# mic4606_power.net
KiCad netlist of a schematic drawn in EAGLE
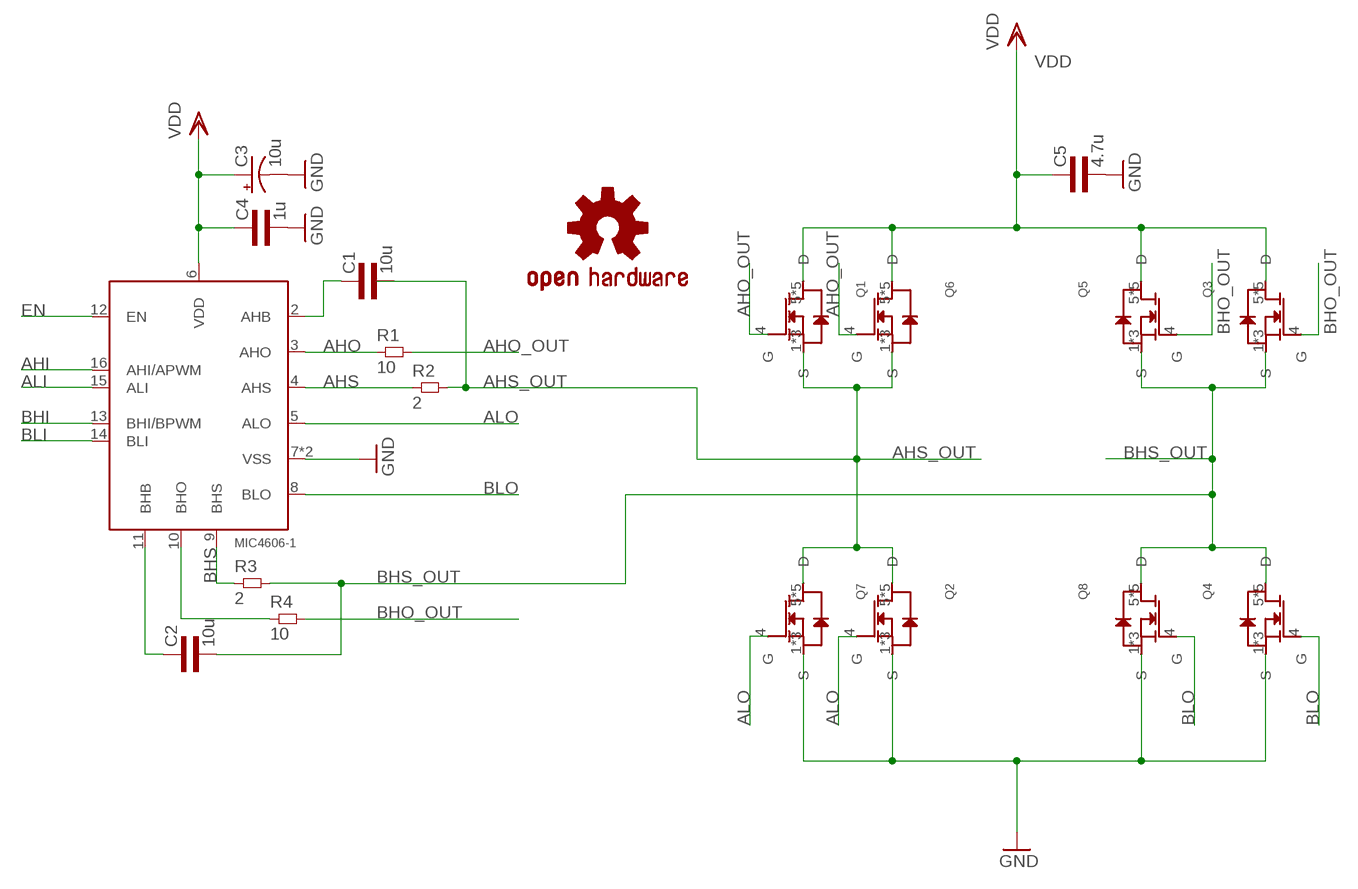
[diagram p0: schematic, sheet 1]

(export (version "E")
  (design (tool "Eeschema 10.0.6"))
  (components
    (comp (ref "C1")
      (value "10u")
      (footprint "eagle-import:0805L3")
      (libsource (lib "eagle-import") (part "CAP0805L3"))
    )
    (comp (ref "C2")
      (value "10u")
      (footprint "eagle-import:0805L3")
      (libsource (lib "eagle-import") (part "CAP0805L3"))
    )
    (comp (ref "C3")
      (value "10u")
      (footprint "eagle-import:E1,8-4")
      (libsource (lib "eagle-import") (part "CPOL-USE1.8-4"))
    )
    (comp (ref "C4")
      (value "1u")
      (footprint "eagle-import:0603L3")
      (libsource (lib "eagle-import") (part "CAP0603L3"))
    )
    (comp (ref "C5")
      (value "4.7u")
      (footprint "eagle-import:0805L3")
      (libsource (lib "eagle-import") (part "CAP0805L3"))
    )
    (comp (ref "LOGO1")
      (value "OSHW-LOGOM")
      (footprint "eagle-import:OSHW-LOGO-M")
      (libsource (lib "eagle-import") (part "OSHW-LOGOM"))
    )
    (comp (ref "MD1")
      (value "MIC4606-1")
      (footprint "eagle-import:QFN44-16LD-PL-2")
      (libsource (lib "eagle-import") (part "MIC4606-1"))
    )
    (comp (ref "Q1")
      (value "CSD18540Q5B")
      (footprint "eagle-import:Q5B")
      (libsource (lib "eagle-import") (part "CSD18540Q5B"))
    )
    (comp (ref "Q2")
      (value "CSD18540Q5B")
      (footprint "eagle-import:Q5B")
      (libsource (lib "eagle-import") (part "CSD18540Q5B"))
    )
    (comp (ref "Q3")
      (value "CSD18540Q5B")
      (footprint "eagle-import:Q5B")
      (libsource (lib "eagle-import") (part "CSD18540Q5B"))
    )
    (comp (ref "Q4")
      (value "CSD18540Q5B")
      (footprint "eagle-import:Q5B")
      (libsource (lib "eagle-import") (part "CSD18540Q5B"))
    )
    (comp (ref "Q5")
      (value "CSD18540Q5B")
      (footprint "eagle-import:Q5B")
      (libsource (lib "eagle-import") (part "CSD18540Q5B"))
    )
    (comp (ref "Q6")
      (value "CSD18540Q5B")
      (footprint "eagle-import:Q5B")
      (libsource (lib "eagle-import") (part "CSD18540Q5B"))
    )
    (comp (ref "Q7")
      (value "CSD18540Q5B")
      (footprint "eagle-import:Q5B")
      (libsource (lib "eagle-import") (part "CSD18540Q5B"))
    )
    (comp (ref "Q8")
      (value "CSD18540Q5B")
      (footprint "eagle-import:Q5B")
      (libsource (lib "eagle-import") (part "CSD18540Q5B"))
    )
    (comp (ref "R1")
      (value "10")
      (footprint "eagle-import:0805L3")
      (libsource (lib "eagle-import") (part "RES0805L3"))
    )
    (comp (ref "R2")
      (value "2")
      (footprint "eagle-import:0805L3")
      (libsource (lib "eagle-import") (part "RES0805L3"))
    )
    (comp (ref "R3")
      (value "2")
      (footprint "eagle-import:0805L3")
      (libsource (lib "eagle-import") (part "RES0805L3"))
    )
    (comp (ref "R4")
      (value "10")
      (footprint "eagle-import:0805L3")
      (libsource (lib "eagle-import") (part "RES0805L3"))
    )
  )
  (nets
    (net (code "1") (name "/AHI") (class "Default")
      (node (ref "MD1") (pin "16") (pinfunction "AHI/APWM_16") (pintype "bidirectional"))
    )
    (net (code "2") (name "/AHO") (class "Default")
      (node (ref "MD1") (pin "3") (pinfunction "AHO_3") (pintype "bidirectional"))
      (node (ref "R1") (pin "1") (pinfunction "1_1") (pintype "bidirectional"))
    )
    (net (code "3") (name "/AHO_OUT") (class "Default")
      (node (ref "Q1") (pin "4") (pinfunction "G_4") (pintype "bidirectional"))
      (node (ref "Q6") (pin "4") (pinfunction "G_4") (pintype "bidirectional"))
      (node (ref "R1") (pin "2") (pinfunction "2_2") (pintype "bidirectional"))
    )
    (net (code "4") (name "/AHS") (class "Default")
      (node (ref "MD1") (pin "4") (pinfunction "AHS_4") (pintype "bidirectional"))
      (node (ref "R2") (pin "1") (pinfunction "1_1") (pintype "bidirectional"))
    )
    (net (code "5") (name "/AHS_OUT") (class "Default")
      (node (ref "C1") (pin "2") (pinfunction "2_2") (pintype "bidirectional"))
      (node (ref "Q1") (pin "1") (pinfunction "S_1") (pintype "bidirectional"))
      (node (ref "Q1") (pin "2") (pinfunction "S_2") (pintype "bidirectional"))
      (node (ref "Q1") (pin "3") (pinfunction "S_3") (pintype "bidirectional"))
      (node (ref "Q2") (pin "5") (pinfunction "D_5") (pintype "bidirectional"))
      (node (ref "Q2") (pin "6") (pinfunction "D_6") (pintype "bidirectional"))
      (node (ref "Q2") (pin "7") (pinfunction "D_7") (pintype "bidirectional"))
      (node (ref "Q2") (pin "8") (pinfunction "D_8") (pintype "bidirectional"))
      (node (ref "Q2") (pin "9") (pinfunction "D_9") (pintype "bidirectional"))
      (node (ref "Q6") (pin "1") (pinfunction "S_1") (pintype "bidirectional"))
      (node (ref "Q6") (pin "2") (pinfunction "S_2") (pintype "bidirectional"))
      (node (ref "Q6") (pin "3") (pinfunction "S_3") (pintype "bidirectional"))
      (node (ref "Q7") (pin "5") (pinfunction "D_5") (pintype "bidirectional"))
      (node (ref "Q7") (pin "6") (pinfunction "D_6") (pintype "bidirectional"))
      (node (ref "Q7") (pin "7") (pinfunction "D_7") (pintype "bidirectional"))
      (node (ref "Q7") (pin "8") (pinfunction "D_8") (pintype "bidirectional"))
      (node (ref "Q7") (pin "9") (pinfunction "D_9") (pintype "bidirectional"))
      (node (ref "R2") (pin "2") (pinfunction "2_2") (pintype "bidirectional"))
    )
    (net (code "6") (name "/ALI") (class "Default")
      (node (ref "MD1") (pin "15") (pinfunction "ALI_15") (pintype "bidirectional"))
    )
    (net (code "7") (name "/ALO") (class "Default")
      (node (ref "MD1") (pin "5") (pinfunction "ALO_5") (pintype "bidirectional"))
      (node (ref "Q2") (pin "4") (pinfunction "G_4") (pintype "bidirectional"))
      (node (ref "Q7") (pin "4") (pinfunction "G_4") (pintype "bidirectional"))
    )
    (net (code "8") (name "/BHI") (class "Default")
      (node (ref "MD1") (pin "13") (pinfunction "BHI/BPWM_13") (pintype "bidirectional"))
    )
    (net (code "9") (name "/BHO_OUT") (class "Default")
      (node (ref "Q3") (pin "4") (pinfunction "G_4") (pintype "bidirectional"))
      (node (ref "Q5") (pin "4") (pinfunction "G_4") (pintype "bidirectional"))
      (node (ref "R4") (pin "2") (pinfunction "2_2") (pintype "bidirectional"))
    )
    (net (code "10") (name "/BHS") (class "Default")
      (node (ref "MD1") (pin "9") (pinfunction "BHS_9") (pintype "bidirectional"))
      (node (ref "R3") (pin "1") (pinfunction "1_1") (pintype "bidirectional"))
    )
    (net (code "11") (name "/BHS_OUT") (class "Default")
      (node (ref "C2") (pin "2") (pinfunction "2_2") (pintype "bidirectional"))
      (node (ref "Q3") (pin "1") (pinfunction "S_1") (pintype "bidirectional"))
      (node (ref "Q3") (pin "2") (pinfunction "S_2") (pintype "bidirectional"))
      (node (ref "Q3") (pin "3") (pinfunction "S_3") (pintype "bidirectional"))
      (node (ref "Q4") (pin "5") (pinfunction "D_5") (pintype "bidirectional"))
      (node (ref "Q4") (pin "6") (pinfunction "D_6") (pintype "bidirectional"))
      (node (ref "Q4") (pin "7") (pinfunction "D_7") (pintype "bidirectional"))
      (node (ref "Q4") (pin "8") (pinfunction "D_8") (pintype "bidirectional"))
      (node (ref "Q4") (pin "9") (pinfunction "D_9") (pintype "bidirectional"))
      (node (ref "Q5") (pin "1") (pinfunction "S_1") (pintype "bidirectional"))
      (node (ref "Q5") (pin "2") (pinfunction "S_2") (pintype "bidirectional"))
      (node (ref "Q5") (pin "3") (pinfunction "S_3") (pintype "bidirectional"))
      (node (ref "Q8") (pin "5") (pinfunction "D_5") (pintype "bidirectional"))
      (node (ref "Q8") (pin "6") (pinfunction "D_6") (pintype "bidirectional"))
      (node (ref "Q8") (pin "7") (pinfunction "D_7") (pintype "bidirectional"))
      (node (ref "Q8") (pin "8") (pinfunction "D_8") (pintype "bidirectional"))
      (node (ref "Q8") (pin "9") (pinfunction "D_9") (pintype "bidirectional"))
      (node (ref "R3") (pin "2") (pinfunction "2_2") (pintype "bidirectional"))
    )
    (net (code "12") (name "/BLI") (class "Default")
      (node (ref "MD1") (pin "14") (pinfunction "BLI_14") (pintype "bidirectional"))
    )
    (net (code "13") (name "/BLO") (class "Default")
      (node (ref "MD1") (pin "8") (pinfunction "BLO_8") (pintype "bidirectional"))
      (node (ref "Q4") (pin "4") (pinfunction "G_4") (pintype "bidirectional"))
      (node (ref "Q8") (pin "4") (pinfunction "G_4") (pintype "bidirectional"))
    )
    (net (code "14") (name "/EN") (class "Default")
      (node (ref "MD1") (pin "12") (pinfunction "EN_12") (pintype "bidirectional"))
    )
    (net (code "15") (name "GND") (class "Default")
      (node (ref "C3") (pin "-") (pinfunction "-_-") (pintype "passive"))
      (node (ref "C4") (pin "P$2") (pinfunction "2_P$2") (pintype "bidirectional"))
      (node (ref "C5") (pin "2") (pinfunction "2_2") (pintype "bidirectional"))
      (node (ref "MD1") (pin "7") (pinfunction "VSS_7") (pintype "bidirectional"))
      (node (ref "MD1") (pin "TP") (pinfunction "VSS_TP") (pintype "bidirectional"))
      (node (ref "Q2") (pin "1") (pinfunction "S_1") (pintype "bidirectional"))
      (node (ref "Q2") (pin "2") (pinfunction "S_2") (pintype "bidirectional"))
      (node (ref "Q2") (pin "3") (pinfunction "S_3") (pintype "bidirectional"))
      (node (ref "Q4") (pin "1") (pinfunction "S_1") (pintype "bidirectional"))
      (node (ref "Q4") (pin "2") (pinfunction "S_2") (pintype "bidirectional"))
      (node (ref "Q4") (pin "3") (pinfunction "S_3") (pintype "bidirectional"))
      (node (ref "Q7") (pin "1") (pinfunction "S_1") (pintype "bidirectional"))
      (node (ref "Q7") (pin "2") (pinfunction "S_2") (pintype "bidirectional"))
      (node (ref "Q7") (pin "3") (pinfunction "S_3") (pintype "bidirectional"))
      (node (ref "Q8") (pin "1") (pinfunction "S_1") (pintype "bidirectional"))
      (node (ref "Q8") (pin "2") (pinfunction "S_2") (pintype "bidirectional"))
      (node (ref "Q8") (pin "3") (pinfunction "S_3") (pintype "bidirectional"))
    )
    (net (code "16") (name "Net-(MD1-AHB)") (class "Default")
      (node (ref "C1") (pin "1") (pinfunction "1_1") (pintype "bidirectional"))
      (node (ref "MD1") (pin "2") (pinfunction "AHB_2") (pintype "bidirectional"))
    )
    (net (code "17") (name "Net-(MD1-BHB)") (class "Default")
      (node (ref "C2") (pin "1") (pinfunction "1_1") (pintype "bidirectional"))
      (node (ref "MD1") (pin "11") (pinfunction "BHB_11") (pintype "bidirectional"))
    )
    (net (code "18") (name "Net-(MD1-BHO)") (class "Default")
      (node (ref "MD1") (pin "10") (pinfunction "BHO_10") (pintype "bidirectional"))
      (node (ref "R4") (pin "1") (pinfunction "1_1") (pintype "bidirectional"))
    )
    (net (code "19") (name "VDD") (class "Default")
      (node (ref "C3") (pin "+") (pinfunction "+_+") (pintype "passive"))
      (node (ref "C4") (pin "P$1") (pinfunction "1_P$1") (pintype "bidirectional"))
      (node (ref "C5") (pin "1") (pinfunction "1_1") (pintype "bidirectional"))
      (node (ref "MD1") (pin "6") (pinfunction "VDD_6") (pintype "bidirectional"))
      (node (ref "Q1") (pin "5") (pinfunction "D_5") (pintype "bidirectional"))
      (node (ref "Q1") (pin "6") (pinfunction "D_6") (pintype "bidirectional"))
      (node (ref "Q1") (pin "7") (pinfunction "D_7") (pintype "bidirectional"))
      (node (ref "Q1") (pin "8") (pinfunction "D_8") (pintype "bidirectional"))
      (node (ref "Q1") (pin "9") (pinfunction "D_9") (pintype "bidirectional"))
      (node (ref "Q3") (pin "5") (pinfunction "D_5") (pintype "bidirectional"))
      (node (ref "Q3") (pin "6") (pinfunction "D_6") (pintype "bidirectional"))
      (node (ref "Q3") (pin "7") (pinfunction "D_7") (pintype "bidirectional"))
      (node (ref "Q3") (pin "8") (pinfunction "D_8") (pintype "bidirectional"))
      (node (ref "Q3") (pin "9") (pinfunction "D_9") (pintype "bidirectional"))
      (node (ref "Q5") (pin "5") (pinfunction "D_5") (pintype "bidirectional"))
      (node (ref "Q5") (pin "6") (pinfunction "D_6") (pintype "bidirectional"))
      (node (ref "Q5") (pin "7") (pinfunction "D_7") (pintype "bidirectional"))
      (node (ref "Q5") (pin "8") (pinfunction "D_8") (pintype "bidirectional"))
      (node (ref "Q5") (pin "9") (pinfunction "D_9") (pintype "bidirectional"))
      (node (ref "Q6") (pin "5") (pinfunction "D_5") (pintype "bidirectional"))
      (node (ref "Q6") (pin "6") (pinfunction "D_6") (pintype "bidirectional"))
      (node (ref "Q6") (pin "7") (pinfunction "D_7") (pintype "bidirectional"))
      (node (ref "Q6") (pin "8") (pinfunction "D_8") (pintype "bidirectional"))
      (node (ref "Q6") (pin "9") (pinfunction "D_9") (pintype "bidirectional"))
    )
  )
)
